# Schmitt_Trigger_Circuit.net
KiCad netlist of a schematic drawn in EasyEDA Pro
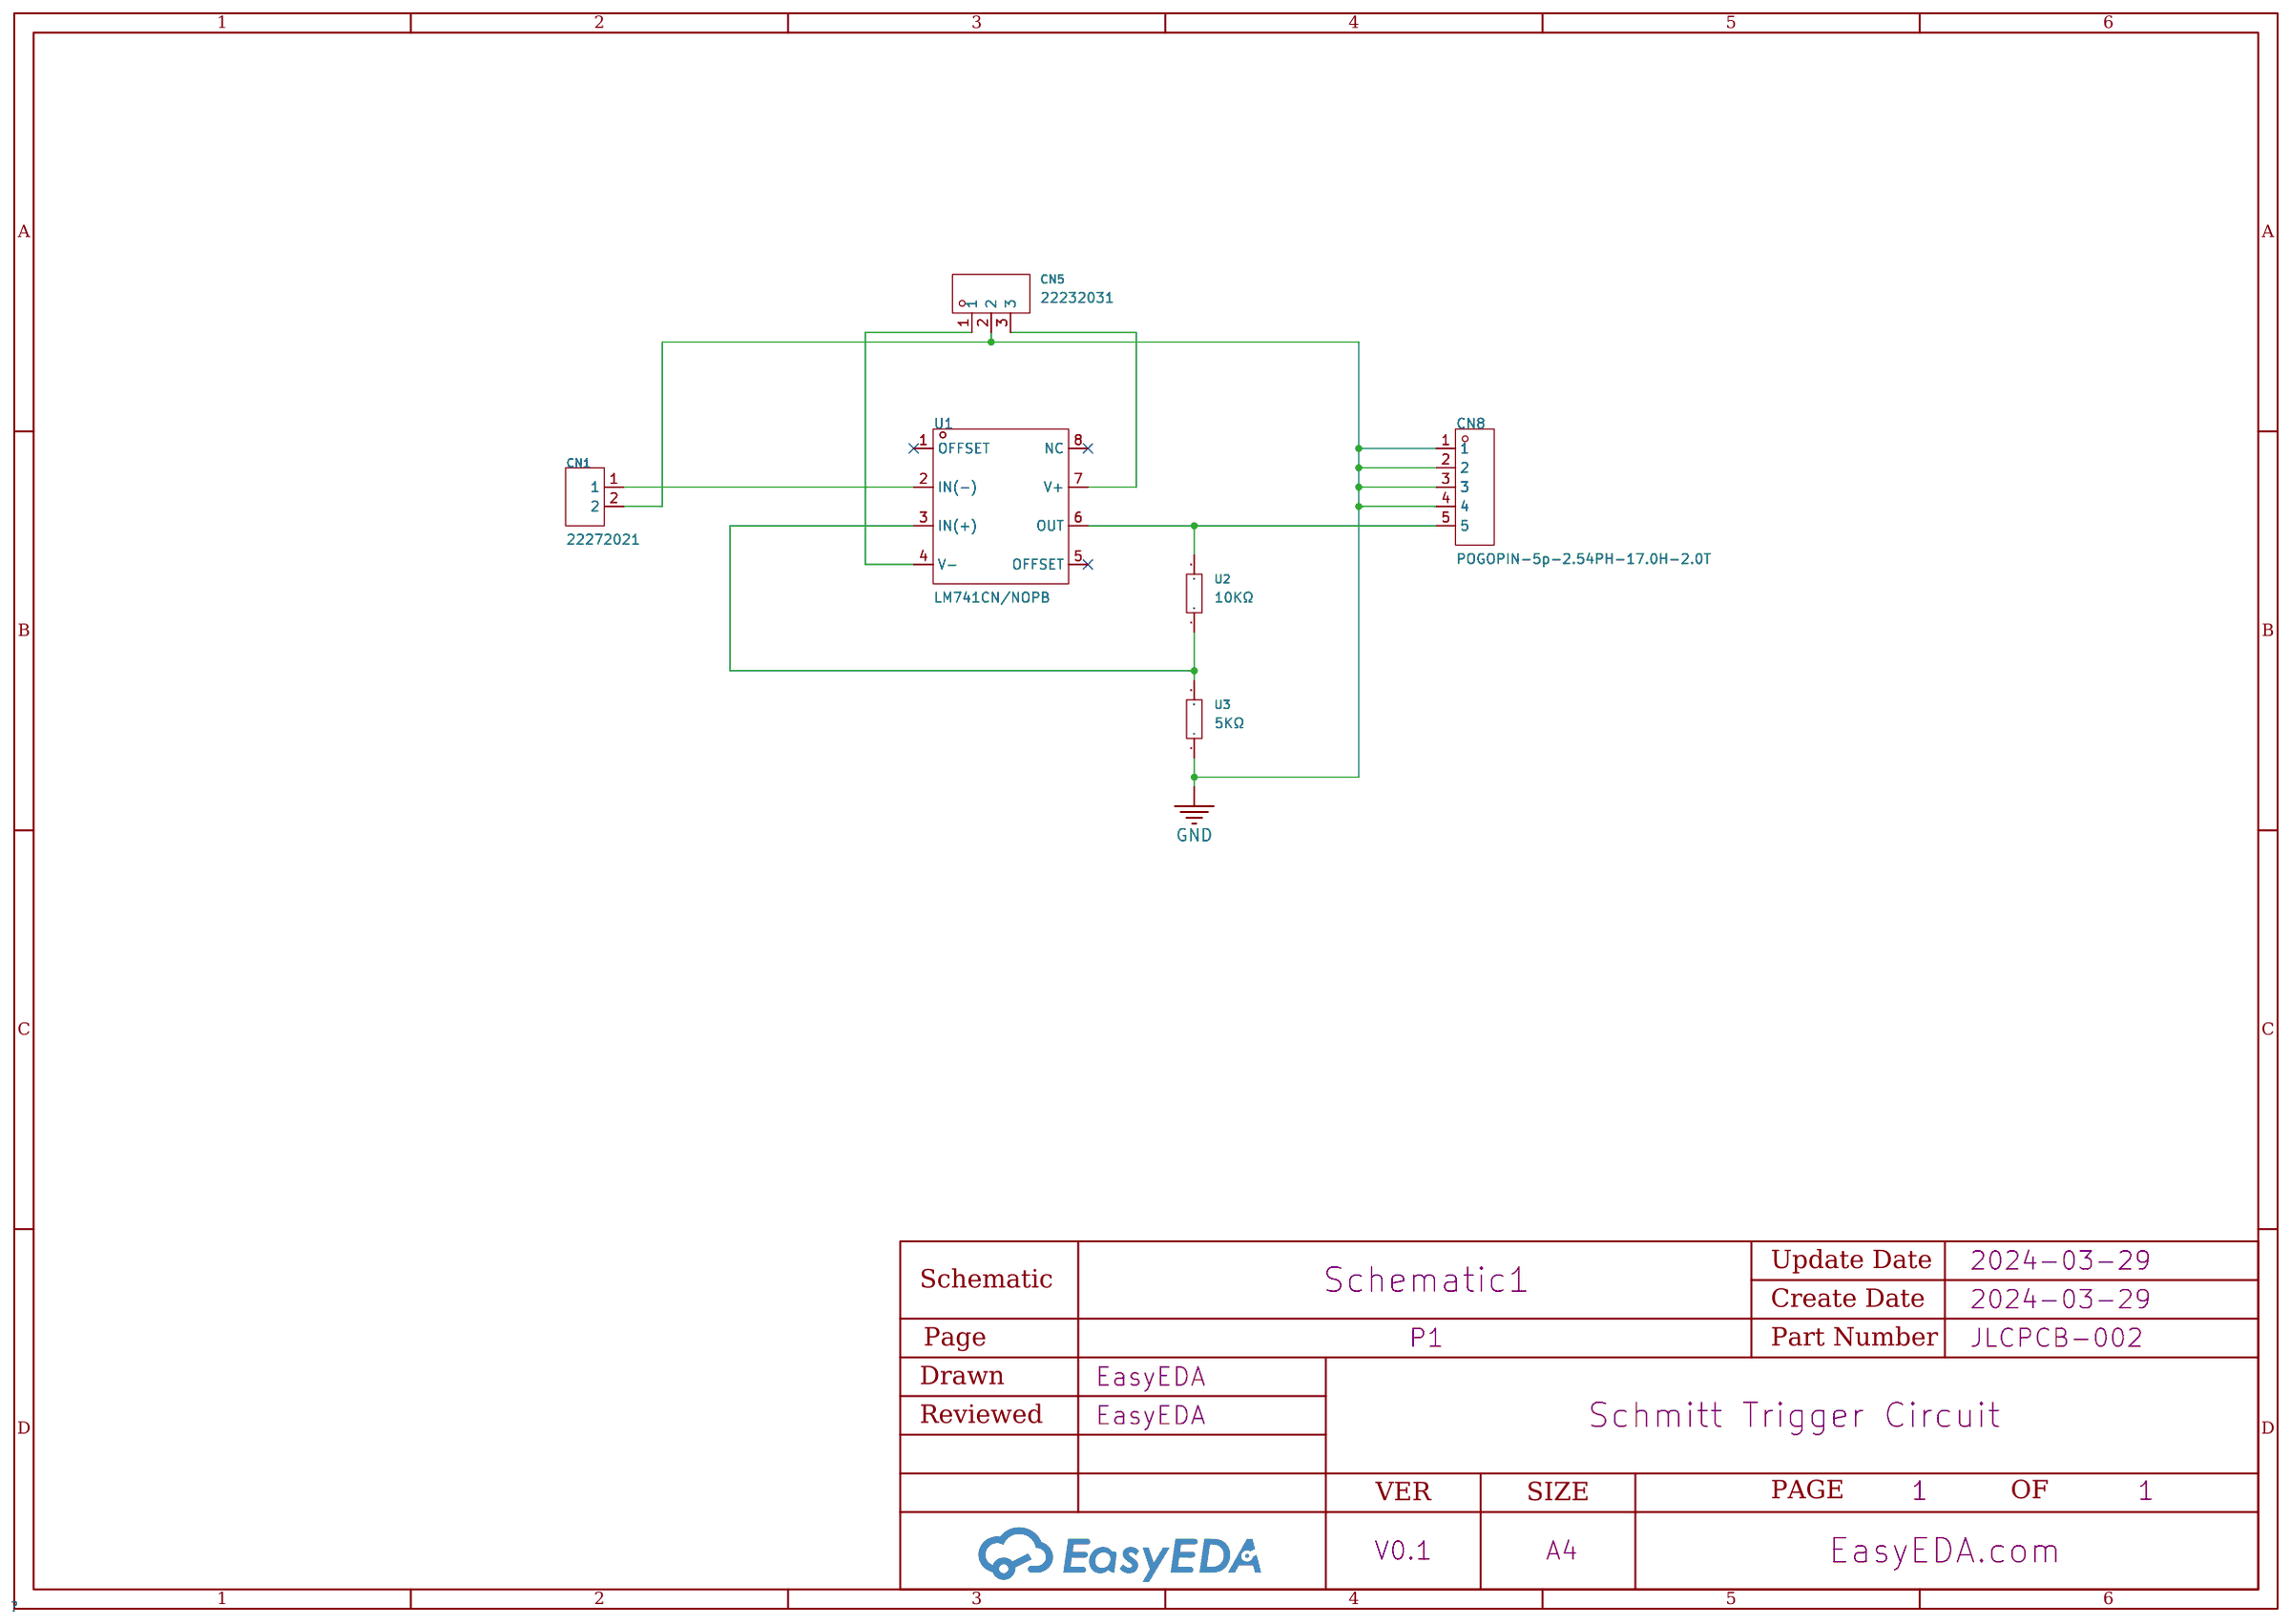
[diagram p0: schematic sheet]

(export (version "E")
  (design (tool "Eeschema 10.0.6"))
  (components
    (comp (ref "CN1")
      (value "22272021")
      (footprint "easyedapro:CONN-TH_22272021")
      (fields (field (name "Manufacturer") "MOLEX"))
      (libsource (lib "easyedapro") (part "22272021"))
    )
    (comp (ref "CN5")
      (value "22232031")
      (footprint "easyedapro:CONN-TH_3P-P2.54_22-23-2031")
      (fields (field (name "Manufacturer") "MOLEX"))
      (libsource (lib "easyedapro") (part "22-23-2031"))
    )
    (comp (ref "CN8")
      (value "POGOPIN-5p-2.54PH-17.0H-2.0T")
      (footprint "easyedapro:CONN-TH_5P-P2.54_POGOPIN-5P-2.54P")
      (libsource (lib "easyedapro") (part "POGOPIN-5P-2.54PH-17.0H-2.0T"))
    )
    (comp (ref "U1")
      (value "LM741CN/NOPB")
      (footprint "easyedapro:DIP-8_L9.8-W6.6-P2.54-LS7.6-BL")
      (fields (field (name "Manufacturer") "TI(德州仪器)"))
      (libsource (lib "easyedapro") (part "LM741CN"))
    )
    (comp (ref "U2")
      (value "10KΩ")
      (footprint "easyedapro:RES-TH_BD3.5-L9.0-P13.00-D0.8")
      (description "Type:Safety Resistor Resistance: Tolerance:±5% Tolerance:±5% Power(Watts):1W")
      (fields (field (name "Manufacturer Part") "FR1WS-5.1Ω±5%") (field (name "Manufacturer") "CCO(千志电子)"))
      (libsource (lib "easyedapro") (part "FR1WS-5.1Ω±5%"))
    )
    (comp (ref "U3")
      (value "5KΩ")
      (footprint "easyedapro:RES-TH_BD3.5-L9.0-P13.00-D0.8")
      (description "Type:Safety Resistor Resistance: Tolerance:±5% Tolerance:±5% Power(Watts):1W")
      (fields (field (name "Manufacturer Part") "FR1WS-5.1Ω±5%") (field (name "Manufacturer") "CCO(千志电子)"))
      (libsource (lib "easyedapro") (part "FR1WS-5.1Ω±5%"))
    )
  )
  (nets
    (net (code "1") (name "GND") (class "Default")
      (node (ref "CN1") (pin "2") (pinfunction "2_2") (pintype "input"))
      (node (ref "CN5") (pin "2") (pinfunction "2_2") (pintype "input"))
      (node (ref "CN8") (pin "1") (pinfunction "1_1") (pintype "input"))
      (node (ref "CN8") (pin "2") (pinfunction "2_2") (pintype "input"))
      (node (ref "CN8") (pin "3") (pinfunction "3_3") (pintype "input"))
      (node (ref "CN8") (pin "4") (pinfunction "4_4") (pintype "input"))
      (node (ref "U3") (pin "1") (pinfunction "1_1") (pintype "input"))
    )
    (net (code "2") (name "Net-(U1-IN(+))") (class "Default")
      (node (ref "U1") (pin "3") (pinfunction "IN(+)_3") (pintype "input"))
      (node (ref "U2") (pin "1") (pinfunction "1_1") (pintype "input"))
      (node (ref "U3") (pin "2") (pinfunction "2_2") (pintype "input"))
    )
    (net (code "3") (name "Net-(U1-IN(-))") (class "Default")
      (node (ref "CN1") (pin "1") (pinfunction "1_1") (pintype "input"))
      (node (ref "U1") (pin "2") (pinfunction "IN(-)_2") (pintype "input"))
    )
    (net (code "4") (name "Net-(U1-OUT)") (class "Default")
      (node (ref "CN8") (pin "5") (pinfunction "5_5") (pintype "input"))
      (node (ref "U1") (pin "6") (pinfunction "OUT_6") (pintype "input"))
      (node (ref "U2") (pin "2") (pinfunction "2_2") (pintype "input"))
    )
    (net (code "5") (name "Net-(U1-V+)") (class "Default")
      (node (ref "CN5") (pin "3") (pinfunction "3_3") (pintype "input"))
      (node (ref "U1") (pin "7") (pinfunction "V+_7") (pintype "input"))
    )
    (net (code "6") (name "Net-(U1-V-)") (class "Default")
      (node (ref "CN5") (pin "1") (pinfunction "1_1") (pintype "input"))
      (node (ref "U1") (pin "4") (pinfunction "V-_4") (pintype "input"))
    )
    (net (code "7") (name "unconnected-(U1-NC-Pad8)") (class "Default")
      (node (ref "U1") (pin "8") (pinfunction "NC_8") (pintype "input+no_connect"))
    )
    (net (code "8") (name "unconnected-(U1-OFFSET-Pad1)") (class "Default")
      (node (ref "U1") (pin "1") (pinfunction "OFFSET_1") (pintype "input+no_connect"))
    )
    (net (code "9") (name "unconnected-(U1-OFFSET-Pad5)") (class "Default")
      (node (ref "U1") (pin "5") (pinfunction "OFFSET_5") (pintype "input+no_connect"))
    )
  )
)
